# SilentStepStick-TMC2130_v10.net
KiCad netlist of a schematic drawn in EAGLE
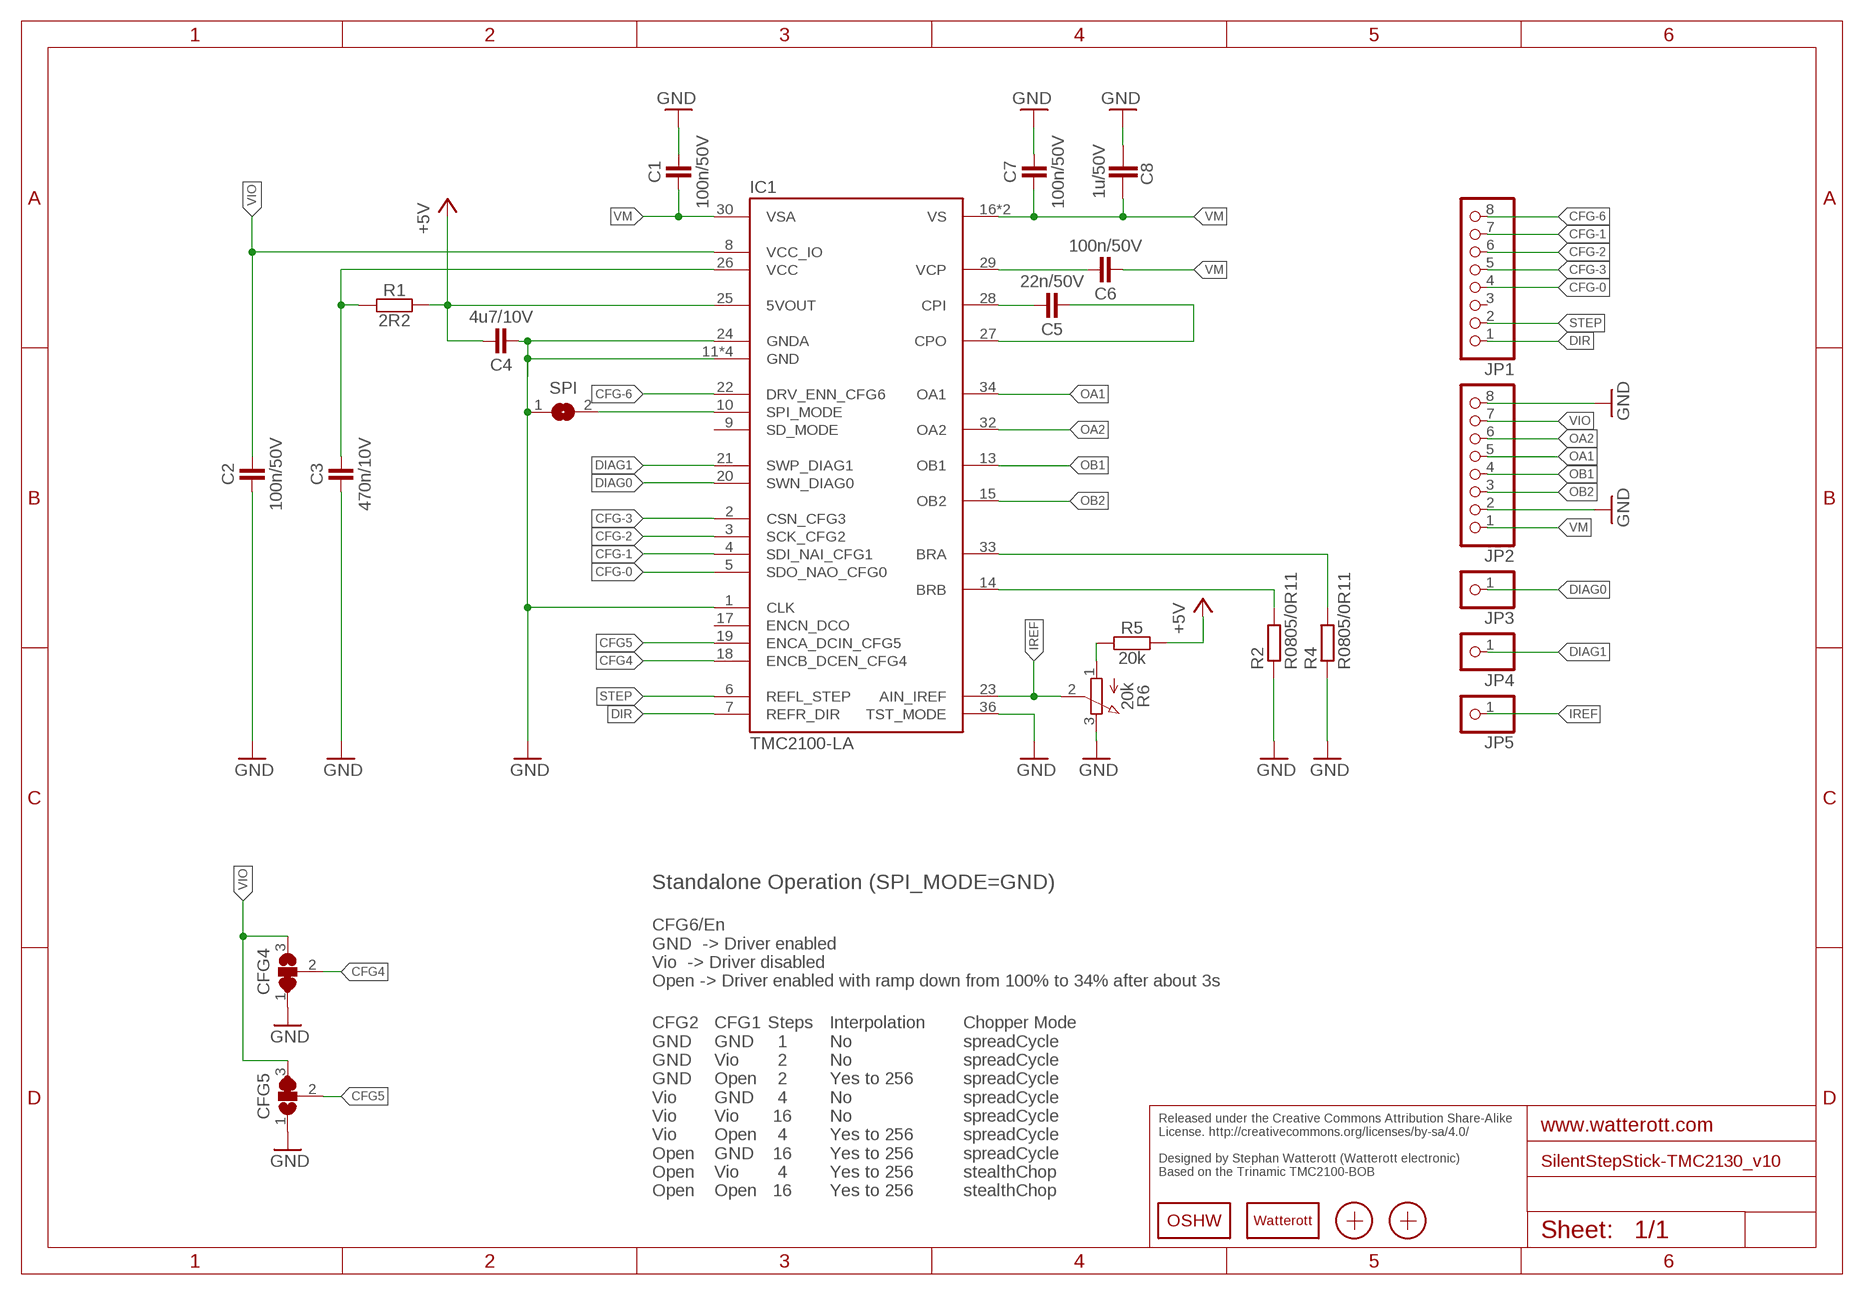
[diagram p0: schematic, sheet 1]

(export (version "E")
  (design (tool "Eeschema 10.0.6"))
  (components
    (comp (ref "C1")
      (value "100n/50V")
      (footprint "eagle-import:C0402")
      (libsource (lib "eagle-import") (part "CAPACITOR-0402"))
    )
    (comp (ref "C2")
      (value "100n/50V")
      (footprint "eagle-import:C0402")
      (libsource (lib "eagle-import") (part "CAPACITOR-0402"))
    )
    (comp (ref "C3")
      (value "470n/10V")
      (footprint "eagle-import:C0402")
      (libsource (lib "eagle-import") (part "CAPACITOR-0402"))
    )
    (comp (ref "C4")
      (value "4u7/10V")
      (footprint "eagle-import:C0402")
      (libsource (lib "eagle-import") (part "CAPACITOR-0402"))
    )
    (comp (ref "C5")
      (value "22n/50V")
      (footprint "eagle-import:C0402")
      (libsource (lib "eagle-import") (part "CAPACITOR-0402"))
    )
    (comp (ref "C6")
      (value "100n/50V")
      (footprint "eagle-import:C0402")
      (libsource (lib "eagle-import") (part "CAPACITOR-0402"))
    )
    (comp (ref "C7")
      (value "100n/50V")
      (footprint "eagle-import:C0402")
      (libsource (lib "eagle-import") (part "CAPACITOR-0402"))
    )
    (comp (ref "C8")
      (value "1u/50V")
      (footprint "eagle-import:C0603")
      (libsource (lib "eagle-import") (part "C-EUC0603"))
    )
    (comp (ref "CFG4")
      (value "JUMPER3-0201")
      (footprint "eagle-import:JUMPER3-0201")
      (libsource (lib "eagle-import") (part "JUMPER3-0201"))
    )
    (comp (ref "CFG5")
      (value "JUMPER3-0201")
      (footprint "eagle-import:JUMPER3-0201")
      (libsource (lib "eagle-import") (part "JUMPER3-0201"))
    )
    (comp (ref "IC1")
      (value "TMC2100-LA")
      (footprint "eagle-import:QFN36-PAD")
      (libsource (lib "eagle-import") (part "TMC2100-LA"))
    )
    (comp (ref "JP1")
      (value "PINHD-1X08_2.54-S")
      (footprint "eagle-import:1X08-S")
      (libsource (lib "eagle-import") (part "PINHD-1X08_2.54-S"))
    )
    (comp (ref "JP2")
      (value "PINHD-1X08_2.54-S")
      (footprint "eagle-import:1X08-S")
      (libsource (lib "eagle-import") (part "PINHD-1X08_2.54-S"))
    )
    (comp (ref "JP3")
      (value "PINHD-1X1")
      (footprint "eagle-import:1X01")
      (libsource (lib "eagle-import") (part "PINHD-1X1"))
    )
    (comp (ref "JP4")
      (value "PINHD-1X1")
      (footprint "eagle-import:1X01")
      (libsource (lib "eagle-import") (part "PINHD-1X1"))
    )
    (comp (ref "JP5")
      (value "PINHD-1X1")
      (footprint "eagle-import:1X01")
      (libsource (lib "eagle-import") (part "PINHD-1X1"))
    )
    (comp (ref "LOGO1")
      (value "OSHW_LOGOX0070")
      (footprint "eagle-import:OSHW_6X70")
      (libsource (lib "eagle-import") (part "OSHW_LOGOX0070"))
    )
    (comp (ref "LOGO2")
      (value "LOGO-S_PLACE_M")
      (footprint "eagle-import:SPARK_TPLACE_M")
      (libsource (lib "eagle-import") (part "LOGO-S_PLACE_M"))
    )
    (comp (ref "R1")
      (value "2R2")
      (footprint "eagle-import:C0402")
      (libsource (lib "eagle-import") (part "RESISTOR-0402"))
    )
    (comp (ref "R2")
      (value "R0805/0R11")
      (footprint "eagle-import:M0805")
      (libsource (lib "eagle-import") (part "R-EU_M0805"))
    )
    (comp (ref "R4")
      (value "R0805/0R11")
      (footprint "eagle-import:M0805")
      (libsource (lib "eagle-import") (part "R-EU_M0805"))
    )
    (comp (ref "R5")
      (value "20k")
      (footprint "eagle-import:C0402")
      (libsource (lib "eagle-import") (part "RESISTOR-0402"))
    )
    (comp (ref "R6")
      (value "20k")
      (footprint "eagle-import:POT_EVM3R")
      (libsource (lib "eagle-import") (part "POTEVM3R"))
    )
    (comp (ref "SPI")
      (value "JUMPER2-0402-NC")
      (footprint "eagle-import:JUMPER2-0402_NC")
      (libsource (lib "eagle-import") (part "JUMPER2-0402-NC"))
    )
    (comp (ref "X1")
      (value "PASSER-07")
      (footprint "eagle-import:PASSER_07MM")
      (libsource (lib "eagle-import") (part "PASSER-07"))
    )
    (comp (ref "X2")
      (value "PASSER-07")
      (footprint "eagle-import:PASSER_07MM")
      (libsource (lib "eagle-import") (part "PASSER-07"))
    )
  )
  (nets
    (net (code "1") (name "+5V") (class "Default")
      (node (ref "C4") (pin "2") (pinfunction "2_2") (pintype "passive"))
      (node (ref "IC1") (pin "25") (pinfunction "5VOUT_25") (pintype "power_in"))
      (node (ref "R1") (pin "2") (pinfunction "2_2") (pintype "passive"))
      (node (ref "R5") (pin "2") (pinfunction "2_2") (pintype "passive"))
    )
    (net (code "2") (name "CFG-0") (class "Default")
      (node (ref "IC1") (pin "5") (pinfunction "SDO_NAO_CFG0_5") (pintype "bidirectional"))
      (node (ref "JP1") (pin "4") (pinfunction "4_4") (pintype "passive"))
    )
    (net (code "3") (name "CFG-1") (class "Default")
      (node (ref "IC1") (pin "4") (pinfunction "SDI_NAI_CFG1_4") (pintype "bidirectional"))
      (node (ref "JP1") (pin "7") (pinfunction "7_7") (pintype "passive"))
    )
    (net (code "4") (name "CFG-2") (class "Default")
      (node (ref "IC1") (pin "3") (pinfunction "SCK_CFG2_3") (pintype "bidirectional"))
      (node (ref "JP1") (pin "6") (pinfunction "6_6") (pintype "passive"))
    )
    (net (code "5") (name "CFG-3") (class "Default")
      (node (ref "IC1") (pin "2") (pinfunction "CSN_CFG3_2") (pintype "bidirectional"))
      (node (ref "JP1") (pin "5") (pinfunction "5_5") (pintype "passive"))
    )
    (net (code "6") (name "CFG-6") (class "Default")
      (node (ref "IC1") (pin "22") (pinfunction "DRV_ENN_CFG6_22") (pintype "bidirectional"))
      (node (ref "JP1") (pin "8") (pinfunction "8_8") (pintype "passive"))
    )
    (net (code "7") (name "CFG4") (class "Default")
      (node (ref "CFG4") (pin "2") (pinfunction "2_2") (pintype "passive"))
      (node (ref "IC1") (pin "18") (pinfunction "ENCB_DCEN_CFG4_18") (pintype "bidirectional"))
    )
    (net (code "8") (name "CFG5") (class "Default")
      (node (ref "CFG5") (pin "2") (pinfunction "2_2") (pintype "passive"))
      (node (ref "IC1") (pin "19") (pinfunction "ENCA_DCIN_CFG5_19") (pintype "bidirectional"))
    )
    (net (code "9") (name "DIAG0") (class "Default")
      (node (ref "IC1") (pin "20") (pinfunction "SWN_DIAG0_20") (pintype "bidirectional"))
      (node (ref "JP3") (pin "1") (pinfunction "1_1") (pintype "passive"))
    )
    (net (code "10") (name "DIAG1") (class "Default")
      (node (ref "IC1") (pin "21") (pinfunction "SWP_DIAG1_21") (pintype "bidirectional"))
      (node (ref "JP4") (pin "1") (pinfunction "1_1") (pintype "passive"))
    )
    (net (code "11") (name "DIR") (class "Default")
      (node (ref "IC1") (pin "7") (pinfunction "REFR_DIR_7") (pintype "bidirectional"))
      (node (ref "JP1") (pin "1") (pinfunction "1_1") (pintype "passive"))
    )
    (net (code "12") (name "GND") (class "Default")
      (node (ref "C1") (pin "2") (pinfunction "2_2") (pintype "passive"))
      (node (ref "C2") (pin "1") (pinfunction "1_1") (pintype "passive"))
      (node (ref "C3") (pin "1") (pinfunction "1_1") (pintype "passive"))
      (node (ref "C4") (pin "1") (pinfunction "1_1") (pintype "passive"))
      (node (ref "C7") (pin "2") (pinfunction "2_2") (pintype "passive"))
      (node (ref "C8") (pin "2") (pinfunction "2_2") (pintype "passive"))
      (node (ref "CFG4") (pin "1") (pinfunction "1_1") (pintype "passive"))
      (node (ref "CFG5") (pin "1") (pinfunction "1_1") (pintype "passive"))
      (node (ref "IC1") (pin "1") (pinfunction "CLK_1") (pintype "bidirectional"))
      (node (ref "IC1") (pin "11") (pinfunction "GND_11") (pintype "power_in"))
      (node (ref "IC1") (pin "12") (pinfunction "GND_12") (pintype "power_in"))
      (node (ref "IC1") (pin "24") (pinfunction "GNDA_24") (pintype "power_in"))
      (node (ref "IC1") (pin "35") (pinfunction "GND_35") (pintype "power_in"))
      (node (ref "IC1") (pin "36") (pinfunction "TST_MODE_36") (pintype "bidirectional"))
      (node (ref "IC1") (pin "TP") (pinfunction "GND_TP") (pintype "power_in"))
      (node (ref "JP2") (pin "2") (pinfunction "2_2") (pintype "passive"))
      (node (ref "JP2") (pin "8") (pinfunction "8_8") (pintype "passive"))
      (node (ref "R2") (pin "1") (pinfunction "1_1") (pintype "passive"))
      (node (ref "R4") (pin "1") (pinfunction "1_1") (pintype "passive"))
      (node (ref "R6") (pin "3") (pinfunction "E_3") (pintype "passive"))
      (node (ref "SPI") (pin "1") (pinfunction "1_1") (pintype "passive"))
    )
    (net (code "13") (name "IREF") (class "Default")
      (node (ref "IC1") (pin "23") (pinfunction "AIN_IREF_23") (pintype "passive"))
      (node (ref "JP5") (pin "1") (pinfunction "1_1") (pintype "passive"))
      (node (ref "R6") (pin "2") (pinfunction "S_2") (pintype "passive"))
    )
    (net (code "14") (name "Net-(IC1-BRA)") (class "Default")
      (node (ref "IC1") (pin "33") (pinfunction "BRA_33") (pintype "output"))
      (node (ref "R4") (pin "2") (pinfunction "2_2") (pintype "passive"))
    )
    (net (code "15") (name "Net-(IC1-BRB)") (class "Default")
      (node (ref "IC1") (pin "14") (pinfunction "BRB_14") (pintype "output"))
      (node (ref "R2") (pin "2") (pinfunction "2_2") (pintype "passive"))
    )
    (net (code "16") (name "Net-(IC1-CPI)") (class "Default")
      (node (ref "C5") (pin "2") (pinfunction "2_2") (pintype "passive"))
      (node (ref "IC1") (pin "28") (pinfunction "CPI_28") (pintype "passive"))
    )
    (net (code "17") (name "Net-(IC1-CPO)") (class "Default")
      (node (ref "C5") (pin "1") (pinfunction "1_1") (pintype "passive"))
      (node (ref "IC1") (pin "27") (pinfunction "CPO_27") (pintype "passive"))
    )
    (net (code "18") (name "Net-(IC1-SPI_MODE)") (class "Default")
      (node (ref "IC1") (pin "10") (pinfunction "SPI_MODE_10") (pintype "bidirectional"))
      (node (ref "SPI") (pin "2") (pinfunction "2_2") (pintype "passive"))
    )
    (net (code "19") (name "Net-(IC1-VCC)") (class "Default")
      (node (ref "C3") (pin "2") (pinfunction "2_2") (pintype "passive"))
      (node (ref "IC1") (pin "26") (pinfunction "VCC_26") (pintype "power_in"))
      (node (ref "R1") (pin "1") (pinfunction "1_1") (pintype "passive"))
    )
    (net (code "20") (name "Net-(IC1-VCP)") (class "Default")
      (node (ref "C6") (pin "2") (pinfunction "2_2") (pintype "passive"))
      (node (ref "IC1") (pin "29") (pinfunction "VCP_29") (pintype "passive"))
    )
    (net (code "21") (name "Net-(R6-A)") (class "Default")
      (node (ref "R5") (pin "1") (pinfunction "1_1") (pintype "passive"))
      (node (ref "R6") (pin "1") (pinfunction "A_1") (pintype "passive"))
    )
    (net (code "22") (name "OA1") (class "Default")
      (node (ref "IC1") (pin "34") (pinfunction "OA1_34") (pintype "output"))
      (node (ref "JP2") (pin "5") (pinfunction "5_5") (pintype "passive"))
    )
    (net (code "23") (name "OA2") (class "Default")
      (node (ref "IC1") (pin "32") (pinfunction "OA2_32") (pintype "output"))
      (node (ref "JP2") (pin "6") (pinfunction "6_6") (pintype "passive"))
    )
    (net (code "24") (name "OB1") (class "Default")
      (node (ref "IC1") (pin "13") (pinfunction "OB1_13") (pintype "output"))
      (node (ref "JP2") (pin "4") (pinfunction "4_4") (pintype "passive"))
    )
    (net (code "25") (name "OB2") (class "Default")
      (node (ref "IC1") (pin "15") (pinfunction "OB2_15") (pintype "output"))
      (node (ref "JP2") (pin "3") (pinfunction "3_3") (pintype "passive"))
    )
    (net (code "26") (name "STEP") (class "Default")
      (node (ref "IC1") (pin "6") (pinfunction "REFL_STEP_6") (pintype "bidirectional"))
      (node (ref "JP1") (pin "2") (pinfunction "2_2") (pintype "passive"))
    )
    (net (code "27") (name "VIO") (class "Default")
      (node (ref "C2") (pin "2") (pinfunction "2_2") (pintype "passive"))
      (node (ref "CFG4") (pin "3") (pinfunction "3_3") (pintype "passive"))
      (node (ref "CFG5") (pin "3") (pinfunction "3_3") (pintype "passive"))
      (node (ref "IC1") (pin "8") (pinfunction "VCC_IO_8") (pintype "power_in"))
      (node (ref "JP2") (pin "7") (pinfunction "7_7") (pintype "passive"))
    )
    (net (code "28") (name "VM") (class "Default")
      (node (ref "C1") (pin "1") (pinfunction "1_1") (pintype "passive"))
      (node (ref "C6") (pin "1") (pinfunction "1_1") (pintype "passive"))
      (node (ref "C7") (pin "1") (pinfunction "1_1") (pintype "passive"))
      (node (ref "C8") (pin "1") (pinfunction "1_1") (pintype "passive"))
      (node (ref "IC1") (pin "16") (pinfunction "VS_16") (pintype "power_in"))
      (node (ref "IC1") (pin "30") (pinfunction "VSA_30") (pintype "power_in"))
      (node (ref "IC1") (pin "31") (pinfunction "VS_31") (pintype "power_in"))
      (node (ref "JP2") (pin "1") (pinfunction "1_1") (pintype "passive"))
    )
    (net (code "29") (name "unconnected-(IC1-ENCN_DCO-Pad17)") (class "Default")
      (node (ref "IC1") (pin "17") (pinfunction "ENCN_DCO_17") (pintype "bidirectional"))
    )
    (net (code "30") (name "unconnected-(IC1-SD_MODE-Pad9)") (class "Default")
      (node (ref "IC1") (pin "9") (pinfunction "SD_MODE_9") (pintype "bidirectional"))
    )
    (net (code "31") (name "unconnected-(JP1-Pad3)") (class "Default")
      (node (ref "JP1") (pin "3") (pinfunction "3_3") (pintype "passive"))
    )
  )
)
